# RECOM_R-78C15-1_0_1A_42V_to_15V.net
KiCad netlist of a schematic drawn in Altium Designer
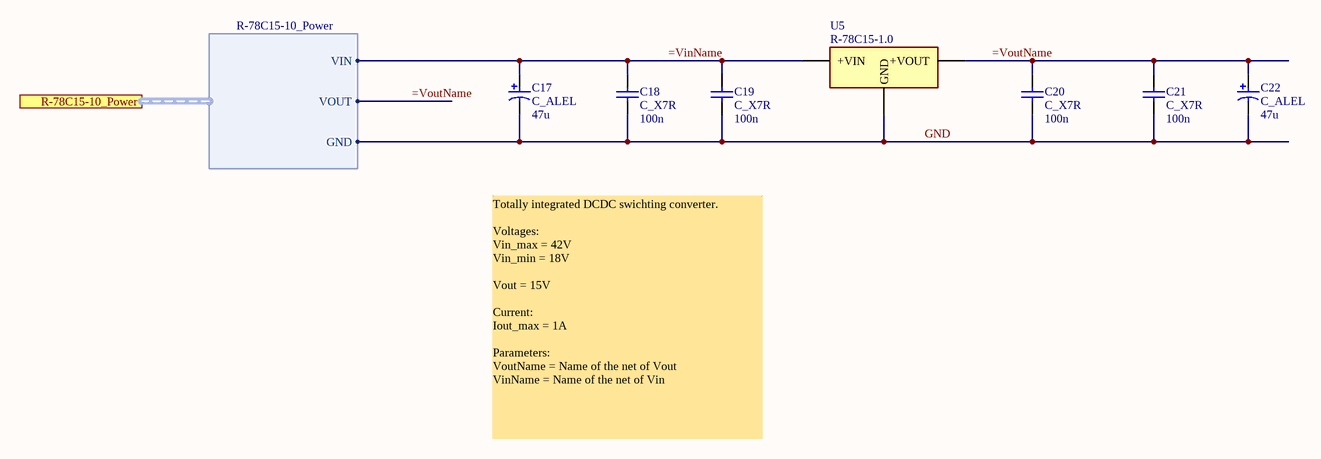
[diagram p0: RECOM_R-78C15-1.0_1A_42V_to_15V.SchDoc]

(export (version "E")
  (design (tool "Eeschema 10.0.6"))
  (components
    (comp (ref "C17")
      (value "C_ALEL")
      (footprint "CAPAE9583X66L")
      (description "Standard Aluminium electrolyt capacitor.")
      (fields
        (field (name "ALTIUM_VALUE") "47u")
        (field (name "MF") "Panasonic")
        (field (name "MPN") "EEE1VA470P")
        (field (name "CREATED") "2019-12-13_Thilo_Wendt")
      )
      (libsource (lib "standard_rlc") (part "C_ALEL_47u"))
    )
    (comp (ref "C18")
      (value "C_X7R")
      (footprint "CAPC3216X180X50NL20T25")
      (fields
        (field (name "ALTIUM_VALUE") "100n")
        (field (name "MF") "KEMET")
        (field (name "MPN") "C1206C104J5RACTU")
        (field (name "CREATED") "2019-12-08_Thilo_Wendt")
      )
      (libsource (lib "standard_rlc") (part "C_X7R_SMALL"))
    )
    (comp (ref "C19")
      (value "C_X7R")
      (footprint "CAPC3216X180X50NL20T25")
      (fields
        (field (name "ALTIUM_VALUE") "100n")
        (field (name "MF") "KEMET")
        (field (name "MPN") "C1206C104J5RACTU")
        (field (name "CREATED") "2019-12-08_Thilo_Wendt")
      )
      (libsource (lib "standard_rlc") (part "C_X7R_SMALL"))
    )
    (comp (ref "C20")
      (value "C_X7R")
      (footprint "CAPC3216X180X50NL20T25")
      (fields
        (field (name "ALTIUM_VALUE") "100n")
        (field (name "MF") "KEMET")
        (field (name "MPN") "C1206C104J5RACTU")
        (field (name "CREATED") "2019-12-08_Thilo_Wendt")
      )
      (libsource (lib "standard_rlc") (part "C_X7R_SMALL"))
    )
    (comp (ref "C21")
      (value "C_X7R")
      (footprint "CAPC3216X180X50NL20T25")
      (fields
        (field (name "ALTIUM_VALUE") "100n")
        (field (name "MF") "KEMET")
        (field (name "MPN") "C1206C104J5RACTU")
        (field (name "CREATED") "2019-12-08_Thilo_Wendt")
      )
      (libsource (lib "standard_rlc") (part "C_X7R_SMALL"))
    )
    (comp (ref "C22")
      (value "C_ALEL")
      (footprint "CAPAE9583X66L")
      (description "Standard Aluminium electrolyt capacitor.")
      (fields
        (field (name "ALTIUM_VALUE") "47u")
        (field (name "MF") "Panasonic")
        (field (name "MPN") "EEE1VA470P")
        (field (name "CREATED") "2019-12-13_Thilo_Wendt")
      )
      (libsource (lib "standard_rlc") (part "C_ALEL_47u"))
    )
    (comp (ref "U5")
      (value "R-78C15-1.0")
      (footprint "R78C1510")
      (description "Swichting Regulator Power Supply with integrated inductor.")
      (fields (field (name "MF") "RECOM Power") (field (name "CREATED") "2019-12-11_Thilo_Wendt"))
      (libsource (lib "power_supply") (part "R-78C15-1.0"))
    )
  )
  (nets
    (net (code "2") (name "/=VinName") (class "Default")
      (node (ref "C17") (pin "1") (pinfunction "1_1") (pintype "passive"))
      (node (ref "C18") (pin "2") (pinfunction "2_2") (pintype "passive"))
      (node (ref "C19") (pin "2") (pinfunction "2_2") (pintype "passive"))
      (node (ref "U5") (pin "1") (pinfunction "+VIN_1") (pintype "power_in"))
    )
    (net (code "3") (name "/=VoutName") (class "Default")
      (node (ref "C20") (pin "2") (pinfunction "2_2") (pintype "passive"))
      (node (ref "C21") (pin "2") (pinfunction "2_2") (pintype "passive"))
      (node (ref "C22") (pin "1") (pinfunction "1_1") (pintype "passive"))
      (node (ref "U5") (pin "3") (pinfunction "+VOUT_3") (pintype "power_in"))
    )
    (net (code "4") (name "/GND") (class "Default")
      (node (ref "C17") (pin "2") (pinfunction "2_2") (pintype "passive"))
      (node (ref "C18") (pin "1") (pinfunction "1_1") (pintype "passive"))
      (node (ref "C19") (pin "1") (pinfunction "1_1") (pintype "passive"))
      (node (ref "C20") (pin "1") (pinfunction "1_1") (pintype "passive"))
      (node (ref "C21") (pin "1") (pinfunction "1_1") (pintype "passive"))
      (node (ref "C22") (pin "2") (pinfunction "2_2") (pintype "passive"))
      (node (ref "U5") (pin "2") (pinfunction "GND_2") (pintype "passive"))
    )
  )
)
